# OUTR.net
KiCad netlist of a schematic drawn in Altium Designer
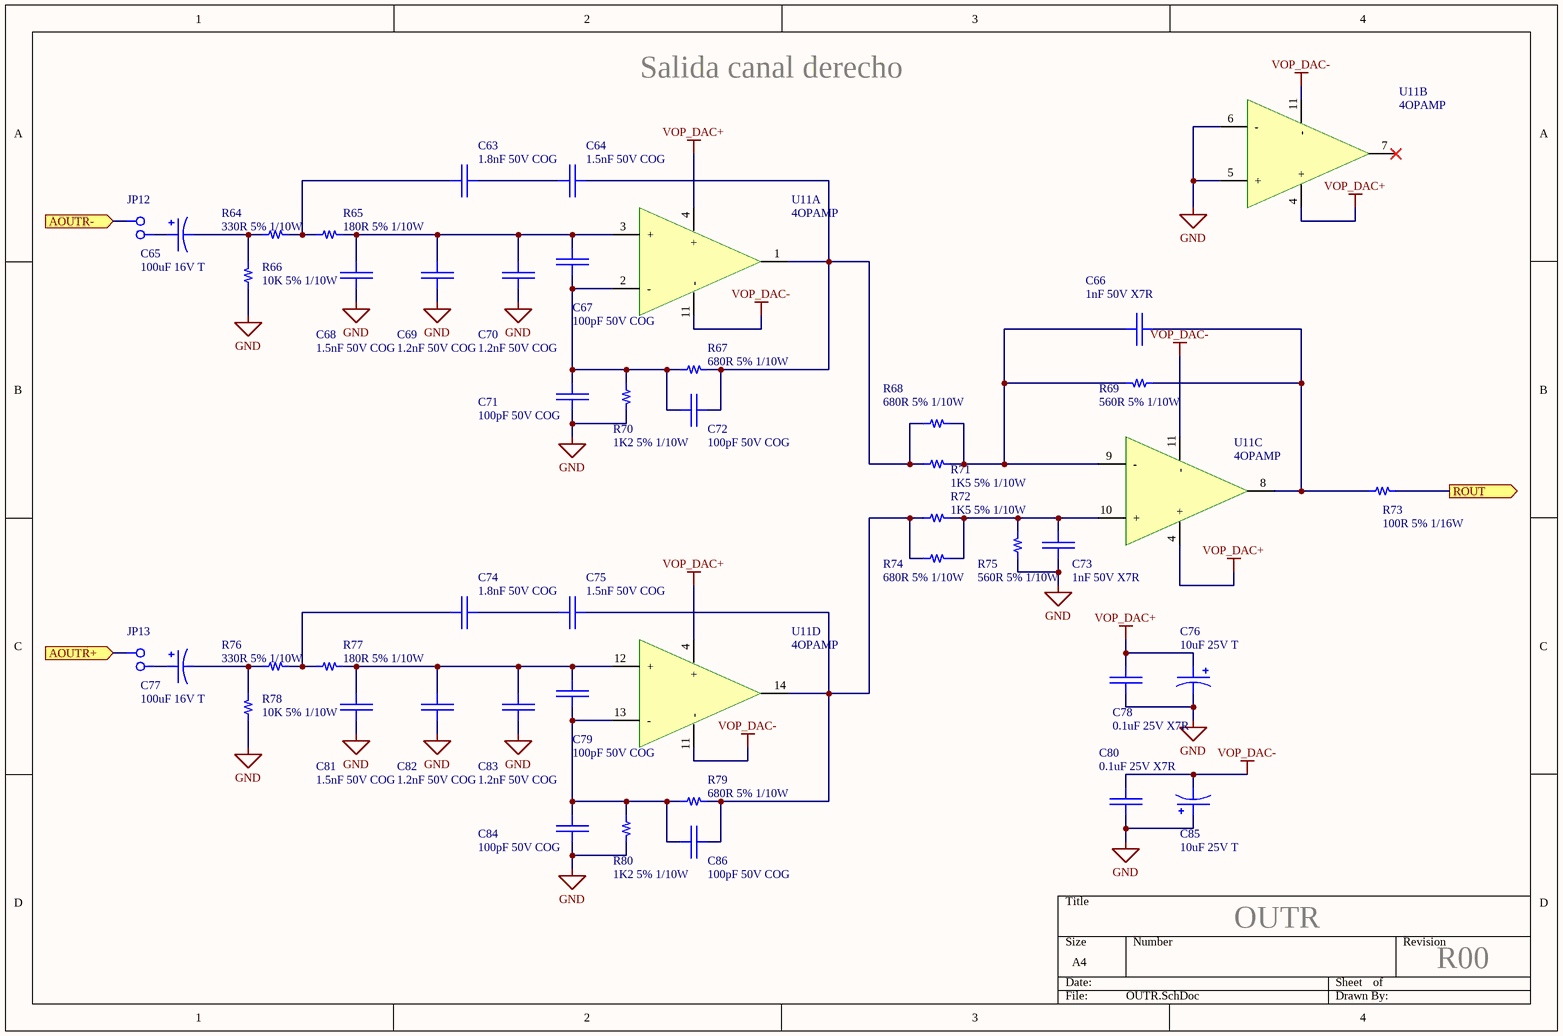
[diagram p0: OUTR.SchDoc]

(export (version "E")
  (design (tool "Eeschema 10.0.6"))
  (components
    (comp (ref "C63")
      (value "1.8nF 50V COG")
      (footprint "C_0805")
      (description "Capacitor de placas paralelas")
      (libsource (lib "Radios_Comunitarias") (part "Capacitor"))
    )
    (comp (ref "C64")
      (value "1.5nF 50V COG")
      (footprint "C_0805")
      (description "Capacitor de placas paralelas")
      (libsource (lib "Radios_Comunitarias") (part "Capacitor"))
    )
    (comp (ref "C65")
      (value "100uF 16V T")
      (footprint "TANT")
      (description "Capacitor polarizado")
      (libsource (lib "Radios_Comunitarias") (part "CapaPol"))
    )
    (comp (ref "C66")
      (value "1nF 50V X7R")
      (footprint "C_0805")
      (description "Capacitor de placas paralelas")
      (libsource (lib "Radios_Comunitarias") (part "Capacitor"))
    )
    (comp (ref "C67")
      (value "100pF 50V COG")
      (footprint "C_0805")
      (description "Capacitor de placas paralelas")
      (libsource (lib "Radios_Comunitarias") (part "Capacitor"))
    )
    (comp (ref "C68")
      (value "1.5nF 50V COG")
      (footprint "C_0805")
      (description "Capacitor de placas paralelas")
      (libsource (lib "Radios_Comunitarias") (part "Capacitor"))
    )
    (comp (ref "C69")
      (value "1.2nF 50V COG")
      (footprint "C_0805")
      (description "Capacitor de placas paralelas")
      (libsource (lib "Radios_Comunitarias") (part "Capacitor"))
    )
    (comp (ref "C70")
      (value "1.2nF 50V COG")
      (footprint "C_0805")
      (description "Capacitor de placas paralelas")
      (libsource (lib "Radios_Comunitarias") (part "Capacitor"))
    )
    (comp (ref "C71")
      (value "100pF 50V COG")
      (footprint "C_0805")
      (description "Capacitor de placas paralelas")
      (libsource (lib "Radios_Comunitarias") (part "Capacitor"))
    )
    (comp (ref "C72")
      (value "100pF 50V COG")
      (footprint "C_0805")
      (description "Capacitor de placas paralelas")
      (libsource (lib "Radios_Comunitarias") (part "Capacitor"))
    )
    (comp (ref "C73")
      (value "1nF 50V X7R")
      (footprint "C_0805")
      (description "Capacitor de placas paralelas")
      (libsource (lib "Radios_Comunitarias") (part "Capacitor"))
    )
    (comp (ref "C74")
      (value "1.8nF 50V COG")
      (footprint "C_0805")
      (description "Capacitor de placas paralelas")
      (libsource (lib "Radios_Comunitarias") (part "Capacitor"))
    )
    (comp (ref "C75")
      (value "1.5nF 50V COG")
      (footprint "C_0805")
      (description "Capacitor de placas paralelas")
      (libsource (lib "Radios_Comunitarias") (part "Capacitor"))
    )
    (comp (ref "C76")
      (value "10uF 25V T")
      (footprint "TANT")
      (description "Capacitor polarizado")
      (libsource (lib "") (part "CapaPol_1"))
    )
    (comp (ref "C77")
      (value "100uF 16V T")
      (footprint "TANT")
      (description "Capacitor polarizado")
      (libsource (lib "Radios_Comunitarias") (part "CapaPol"))
    )
    (comp (ref "C78")
      (value "0.1uF 25V X7R")
      (footprint "C_0805")
      (description "Capacitor de placas paralelas")
      (libsource (lib "Radios_Comunitarias") (part "Capacitor"))
    )
    (comp (ref "C79")
      (value "100pF 50V COG")
      (footprint "C_0805")
      (description "Capacitor de placas paralelas")
      (libsource (lib "Radios_Comunitarias") (part "Capacitor"))
    )
    (comp (ref "C80")
      (value "0.1uF 25V X7R")
      (footprint "C_0805")
      (description "Capacitor de placas paralelas")
      (libsource (lib "Radios_Comunitarias") (part "Capacitor"))
    )
    (comp (ref "C81")
      (value "1.5nF 50V COG")
      (footprint "C_0805")
      (description "Capacitor de placas paralelas")
      (libsource (lib "Radios_Comunitarias") (part "Capacitor"))
    )
    (comp (ref "C82")
      (value "1.2nF 50V COG")
      (footprint "C_0805")
      (description "Capacitor de placas paralelas")
      (libsource (lib "Radios_Comunitarias") (part "Capacitor"))
    )
    (comp (ref "C83")
      (value "1.2nF 50V COG")
      (footprint "C_0805")
      (description "Capacitor de placas paralelas")
      (libsource (lib "Radios_Comunitarias") (part "Capacitor"))
    )
    (comp (ref "C84")
      (value "100pF 50V COG")
      (footprint "C_0805")
      (description "Capacitor de placas paralelas")
      (libsource (lib "Radios_Comunitarias") (part "Capacitor"))
    )
    (comp (ref "C85")
      (value "10uF 25V T")
      (footprint "TANT")
      (description "Capacitor polarizado")
      (libsource (lib "") (part "CapaPol_1"))
    )
    (comp (ref "C86")
      (value "100pF 50V COG")
      (footprint "C_0805")
      (description "Capacitor de placas paralelas")
      (libsource (lib "Radios_Comunitarias") (part "Capacitor"))
    )
    (comp (ref "JP12")
      (value "Jumper 2x1")
      (footprint "Conn_2_1")
      (libsource (lib "Radios_Comunitarias") (part "Jumper 2x1"))
    )
    (comp (ref "JP13")
      (value "Jumper 2x1")
      (footprint "Conn_2_1")
      (libsource (lib "Radios_Comunitarias") (part "Jumper 2x1"))
    )
    (comp (ref "R64")
      (value "330R 5% 1/10W")
      (footprint "R_0805")
      (description "Resistencia")
      (libsource (lib "Radios_Comunitarias") (part "Resistor"))
    )
    (comp (ref "R65")
      (value "180R 5% 1/10W")
      (footprint "R_0805")
      (description "Resistencia")
      (libsource (lib "Radios_Comunitarias") (part "Resistor"))
    )
    (comp (ref "R66")
      (value "10K 5% 1/10W")
      (footprint "R_0805")
      (description "Resistencia")
      (libsource (lib "Radios_Comunitarias") (part "Resistor"))
    )
    (comp (ref "R67")
      (value "680R 5% 1/10W")
      (footprint "R_0805")
      (description "Resistencia")
      (libsource (lib "Radios_Comunitarias") (part "Resistor"))
    )
    (comp (ref "R68")
      (value "680R 5% 1/10W")
      (footprint "R_0805")
      (description "Resistencia")
      (libsource (lib "Radios_Comunitarias") (part "Resistor"))
    )
    (comp (ref "R69")
      (value "560R 5% 1/10W")
      (footprint "R_0805")
      (description "Resistencia")
      (libsource (lib "Radios_Comunitarias") (part "Resistor"))
    )
    (comp (ref "R70")
      (value "1K2 5% 1/10W")
      (footprint "R_0805")
      (description "Resistencia")
      (libsource (lib "Radios_Comunitarias") (part "Resistor"))
    )
    (comp (ref "R71")
      (value "1K5 5% 1/10W")
      (footprint "R_0805")
      (description "Resistencia")
      (libsource (lib "Radios_Comunitarias") (part "Resistor"))
    )
    (comp (ref "R72")
      (value "1K5 5% 1/10W")
      (footprint "R_0805")
      (description "Resistencia")
      (libsource (lib "Radios_Comunitarias") (part "Resistor"))
    )
    (comp (ref "R73")
      (value "100R 5% 1/16W")
      (footprint "R_0805")
      (description "Resistencia")
      (libsource (lib "Radios_Comunitarias") (part "Resistor"))
    )
    (comp (ref "R74")
      (value "680R 5% 1/10W")
      (footprint "R_0805")
      (description "Resistencia")
      (libsource (lib "Radios_Comunitarias") (part "Resistor"))
    )
    (comp (ref "R75")
      (value "560R 5% 1/10W")
      (footprint "R_0805")
      (description "Resistencia")
      (libsource (lib "Radios_Comunitarias") (part "Resistor"))
    )
    (comp (ref "R76")
      (value "330R 5% 1/10W")
      (footprint "R_0805")
      (description "Resistencia")
      (libsource (lib "Radios_Comunitarias") (part "Resistor"))
    )
    (comp (ref "R77")
      (value "180R 5% 1/10W")
      (footprint "R_0805")
      (description "Resistencia")
      (libsource (lib "Radios_Comunitarias") (part "Resistor"))
    )
    (comp (ref "R78")
      (value "10K 5% 1/10W")
      (footprint "R_0805")
      (description "Resistencia")
      (libsource (lib "Radios_Comunitarias") (part "Resistor"))
    )
    (comp (ref "R79")
      (value "680R 5% 1/10W")
      (footprint "R_0805")
      (description "Resistencia")
      (libsource (lib "Radios_Comunitarias") (part "Resistor"))
    )
    (comp (ref "R80")
      (value "1K2 5% 1/10W")
      (footprint "R_0805")
      (description "Resistencia")
      (libsource (lib "Radios_Comunitarias") (part "Resistor"))
    )
    (comp (ref "U11")
      (value "4OPAMP")
      (footprint "SOIC14")
      (description "Integrado con 4 operacionales")
      (libsource (lib "Radios_Comunitarias") (part "4OPAMP"))
    )
  )
  (nets
    (net (code "1") (name "/AOUTR+") (class "Default")
      (node (ref "JP13") (pin "1") (pinfunction "1_1") (pintype "passive"))
    )
    (net (code "2") (name "/AOUTR-") (class "Default")
      (node (ref "JP12") (pin "1") (pinfunction "1_1") (pintype "passive"))
    )
    (net (code "3") (name "/ROUT") (class "Default")
      (node (ref "R73") (pin "2") (pinfunction "2_2") (pintype "passive"))
    )
    (net (code "4") (name "GND") (class "Default")
      (node (ref "C68") (pin "1") (pinfunction "1_1") (pintype "passive"))
      (node (ref "C69") (pin "1") (pinfunction "1_1") (pintype "passive"))
      (node (ref "C70") (pin "1") (pinfunction "1_1") (pintype "passive"))
      (node (ref "C71") (pin "2") (pinfunction "2_2") (pintype "passive"))
      (node (ref "C73") (pin "2") (pinfunction "2_2") (pintype "passive"))
      (node (ref "C76") (pin "2") (pinfunction "2_2") (pintype "passive"))
      (node (ref "C78") (pin "2") (pinfunction "2_2") (pintype "passive"))
      (node (ref "C80") (pin "2") (pinfunction "2_2") (pintype "passive"))
      (node (ref "C81") (pin "1") (pinfunction "1_1") (pintype "passive"))
      (node (ref "C82") (pin "1") (pinfunction "1_1") (pintype "passive"))
      (node (ref "C83") (pin "1") (pinfunction "1_1") (pintype "passive"))
      (node (ref "C84") (pin "2") (pinfunction "2_2") (pintype "passive"))
      (node (ref "C85") (pin "1") (pinfunction "1_1") (pintype "passive"))
      (node (ref "R66") (pin "1") (pinfunction "1_1") (pintype "passive"))
      (node (ref "R70") (pin "2") (pinfunction "2_2") (pintype "passive"))
      (node (ref "R75") (pin "1") (pinfunction "1_1") (pintype "passive"))
      (node (ref "R78") (pin "1") (pinfunction "1_1") (pintype "passive"))
      (node (ref "R80") (pin "2") (pinfunction "2_2") (pintype "passive"))
      (node (ref "U11") (pin "5") (pinfunction "+_5") (pintype "passive"))
      (node (ref "U11") (pin "6") (pinfunction "-_6") (pintype "passive"))
    )
    (net (code "5") (name "Net-(C63-Pad1)") (class "Default")
      (node (ref "C63") (pin "1") (pinfunction "1_1") (pintype "passive"))
      (node (ref "C64") (pin "2") (pinfunction "2_2") (pintype "passive"))
    )
    (net (code "6") (name "Net-(C63-Pad2)") (class "Default")
      (node (ref "C63") (pin "2") (pinfunction "2_2") (pintype "passive"))
      (node (ref "R64") (pin "2") (pinfunction "2_2") (pintype "passive"))
      (node (ref "R65") (pin "1") (pinfunction "1_1") (pintype "passive"))
    )
    (net (code "7") (name "Net-(C65-Pad1)") (class "Default")
      (node (ref "C65") (pin "1") (pinfunction "1_1") (pintype "passive"))
      (node (ref "JP12") (pin "2") (pinfunction "2_2") (pintype "passive"))
    )
    (net (code "8") (name "Net-(C65-Pad2)") (class "Default")
      (node (ref "C65") (pin "2") (pinfunction "2_2") (pintype "passive"))
      (node (ref "R64") (pin "1") (pinfunction "1_1") (pintype "passive"))
      (node (ref "R66") (pin "2") (pinfunction "2_2") (pintype "passive"))
    )
    (net (code "9") (name "Net-(C66-Pad1)") (class "Default")
      (node (ref "C66") (pin "1") (pinfunction "1_1") (pintype "passive"))
      (node (ref "R68") (pin "2") (pinfunction "2_2") (pintype "passive"))
      (node (ref "R69") (pin "2") (pinfunction "2_2") (pintype "passive"))
      (node (ref "R71") (pin "2") (pinfunction "2_2") (pintype "passive"))
      (node (ref "U11") (pin "9") (pinfunction "-_9") (pintype "passive"))
    )
    (net (code "10") (name "Net-(C67-Pad1)") (class "Default")
      (node (ref "C67") (pin "1") (pinfunction "1_1") (pintype "passive"))
      (node (ref "C68") (pin "2") (pinfunction "2_2") (pintype "passive"))
      (node (ref "C69") (pin "2") (pinfunction "2_2") (pintype "passive"))
      (node (ref "C70") (pin "2") (pinfunction "2_2") (pintype "passive"))
      (node (ref "R65") (pin "2") (pinfunction "2_2") (pintype "passive"))
      (node (ref "U11") (pin "3") (pinfunction "+_3") (pintype "passive"))
    )
    (net (code "11") (name "Net-(C67-Pad2)") (class "Default")
      (node (ref "C67") (pin "2") (pinfunction "2_2") (pintype "passive"))
      (node (ref "C71") (pin "1") (pinfunction "1_1") (pintype "passive"))
      (node (ref "C72") (pin "1") (pinfunction "1_1") (pintype "passive"))
      (node (ref "R67") (pin "1") (pinfunction "1_1") (pintype "passive"))
      (node (ref "R70") (pin "1") (pinfunction "1_1") (pintype "passive"))
      (node (ref "U11") (pin "2") (pinfunction "-_2") (pintype "passive"))
    )
    (net (code "12") (name "Net-(C73-Pad1)") (class "Default")
      (node (ref "C73") (pin "1") (pinfunction "1_1") (pintype "passive"))
      (node (ref "R72") (pin "2") (pinfunction "2_2") (pintype "passive"))
      (node (ref "R74") (pin "2") (pinfunction "2_2") (pintype "passive"))
      (node (ref "R75") (pin "2") (pinfunction "2_2") (pintype "passive"))
      (node (ref "U11") (pin "10") (pinfunction "+_10") (pintype "passive"))
    )
    (net (code "13") (name "Net-(C74-Pad1)") (class "Default")
      (node (ref "C74") (pin "1") (pinfunction "1_1") (pintype "passive"))
      (node (ref "C75") (pin "2") (pinfunction "2_2") (pintype "passive"))
    )
    (net (code "14") (name "Net-(C74-Pad2)") (class "Default")
      (node (ref "C74") (pin "2") (pinfunction "2_2") (pintype "passive"))
      (node (ref "R76") (pin "2") (pinfunction "2_2") (pintype "passive"))
      (node (ref "R77") (pin "1") (pinfunction "1_1") (pintype "passive"))
    )
    (net (code "15") (name "Net-(C77-Pad1)") (class "Default")
      (node (ref "C77") (pin "1") (pinfunction "1_1") (pintype "passive"))
      (node (ref "JP13") (pin "2") (pinfunction "2_2") (pintype "passive"))
    )
    (net (code "16") (name "Net-(C77-Pad2)") (class "Default")
      (node (ref "C77") (pin "2") (pinfunction "2_2") (pintype "passive"))
      (node (ref "R76") (pin "1") (pinfunction "1_1") (pintype "passive"))
      (node (ref "R78") (pin "2") (pinfunction "2_2") (pintype "passive"))
    )
    (net (code "17") (name "Net-(C79-Pad1)") (class "Default")
      (node (ref "C79") (pin "1") (pinfunction "1_1") (pintype "passive"))
      (node (ref "C81") (pin "2") (pinfunction "2_2") (pintype "passive"))
      (node (ref "C82") (pin "2") (pinfunction "2_2") (pintype "passive"))
      (node (ref "C83") (pin "2") (pinfunction "2_2") (pintype "passive"))
      (node (ref "R77") (pin "2") (pinfunction "2_2") (pintype "passive"))
      (node (ref "U11") (pin "12") (pinfunction "+_12") (pintype "passive"))
    )
    (net (code "18") (name "Net-(C79-Pad2)") (class "Default")
      (node (ref "C79") (pin "2") (pinfunction "2_2") (pintype "passive"))
      (node (ref "C84") (pin "1") (pinfunction "1_1") (pintype "passive"))
      (node (ref "C86") (pin "1") (pinfunction "1_1") (pintype "passive"))
      (node (ref "R79") (pin "1") (pinfunction "1_1") (pintype "passive"))
      (node (ref "R80") (pin "1") (pinfunction "1_1") (pintype "passive"))
      (node (ref "U11") (pin "13") (pinfunction "-_13") (pintype "passive"))
    )
    (net (code "19") (name "Net-(U11A-OUT)") (class "Default")
      (node (ref "C64") (pin "1") (pinfunction "1_1") (pintype "passive"))
      (node (ref "C72") (pin "2") (pinfunction "2_2") (pintype "passive"))
      (node (ref "R67") (pin "2") (pinfunction "2_2") (pintype "passive"))
      (node (ref "R68") (pin "1") (pinfunction "1_1") (pintype "passive"))
      (node (ref "R71") (pin "1") (pinfunction "1_1") (pintype "passive"))
      (node (ref "U11") (pin "1") (pinfunction "OUT_1") (pintype "passive"))
    )
    (net (code "20") (name "Net-(U11C-OUT)") (class "Default")
      (node (ref "C66") (pin "2") (pinfunction "2_2") (pintype "passive"))
      (node (ref "R69") (pin "1") (pinfunction "1_1") (pintype "passive"))
      (node (ref "R73") (pin "1") (pinfunction "1_1") (pintype "passive"))
      (node (ref "U11") (pin "8") (pinfunction "OUT_8") (pintype "passive"))
    )
    (net (code "21") (name "Net-(U11D-OUT)") (class "Default")
      (node (ref "C75") (pin "1") (pinfunction "1_1") (pintype "passive"))
      (node (ref "C86") (pin "2") (pinfunction "2_2") (pintype "passive"))
      (node (ref "R72") (pin "1") (pinfunction "1_1") (pintype "passive"))
      (node (ref "R74") (pin "1") (pinfunction "1_1") (pintype "passive"))
      (node (ref "R79") (pin "2") (pinfunction "2_2") (pintype "passive"))
      (node (ref "U11") (pin "14") (pinfunction "OUT_14") (pintype "passive"))
    )
    (net (code "22") (name "VOP_DAC+") (class "Default")
      (node (ref "C76") (pin "1") (pinfunction "1_1") (pintype "passive"))
      (node (ref "C78") (pin "1") (pinfunction "1_1") (pintype "passive"))
      (node (ref "U11") (pin "4") (pinfunction "+_4") (pintype "power_in"))
    )
    (net (code "23") (name "VOP_DAC-") (class "Default")
      (node (ref "C80") (pin "1") (pinfunction "1_1") (pintype "passive"))
      (node (ref "C85") (pin "2") (pinfunction "2_2") (pintype "passive"))
      (node (ref "U11") (pin "11") (pinfunction "-_11") (pintype "passive"))
    )
    (net (code "24") (name "unconnected-(U11B-OUT-Pad7)") (class "Default")
      (node (ref "U11") (pin "7") (pinfunction "OUT_7") (pintype "passive+no_connect"))
    )
  )
)
